# Oscillator.net
KiCad netlist of a schematic drawn in Altium Designer
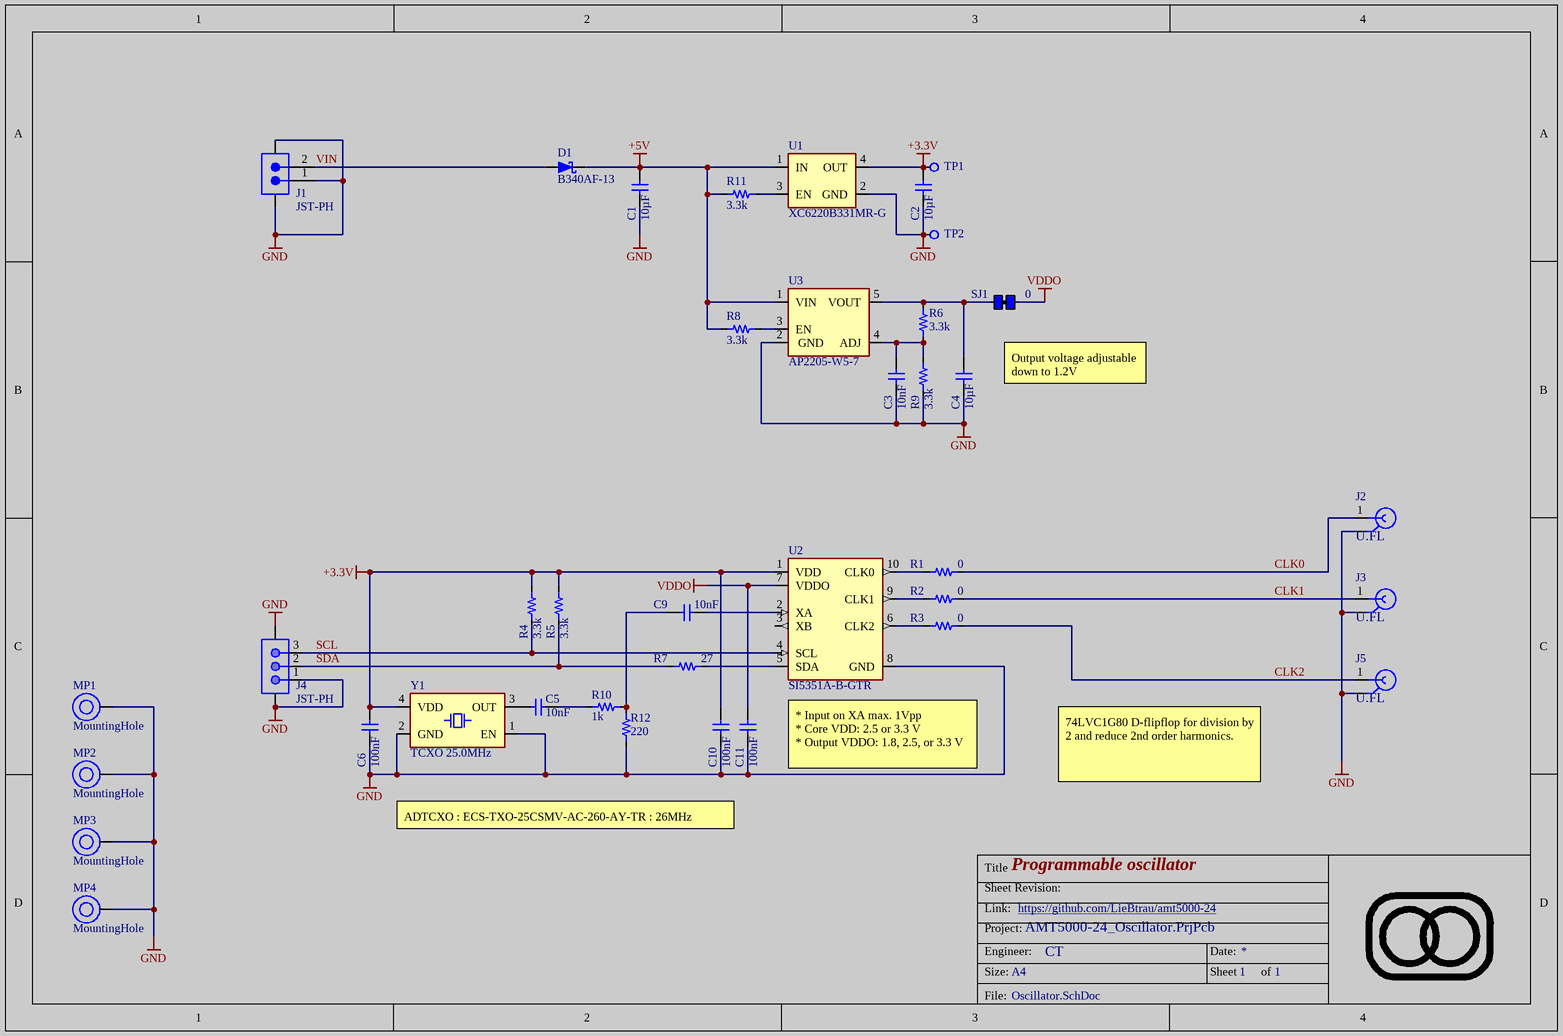
[diagram p0: Oscillator.SchDoc]

(export (version "E")
  (design (tool "Eeschema 10.0.6"))
  (components
    (comp (ref "C1")
      (value "10µF")
      (footprint "1206-C-N")
      (description "WCAP-CSGP Multilayer Ceramic Chip Capacitor, General Purpose, size 1206, X7R, 10µF, 10VDC")
      (fields (field (name "JLCPCB PART #") "C70462") (field (name "TOLERANCE") "10%"))
      (libsource (lib "7c7 Engineering") (part "CAP-NP-2"))
    )
    (comp (ref "C2")
      (value "10µF")
      (footprint "1206-C-N")
      (description "WCAP-CSGP Multilayer Ceramic Chip Capacitor, General Purpose, size 1206, X7R, 10µF, 10VDC")
      (fields (field (name "JLCPCB PART #") "C70462") (field (name "TOLERANCE") "10%"))
      (libsource (lib "7c7 Engineering") (part "CAP-NP-2"))
    )
    (comp (ref "C3")
      (value "10nF")
      (footprint "0603-C-N")
      (description "Multilayer Ceramic Capacitor, Grm Series, 0.01 F, 5%, C0g / Np0, 50 V, 0603 [1608 Metric]")
      (fields (field (name "VOLTAGE") "50V") (field (name "TOLERANCE") "5%"))
      (libsource (lib "7c7 Engineering") (part "CAP-NP-2"))
    )
    (comp (ref "C4")
      (value "10µF")
      (footprint "1206-C-N")
      (description "WCAP-CSGP Multilayer Ceramic Chip Capacitor, General Purpose, size 1206, X7R, 10µF, 10VDC")
      (fields (field (name "JLCPCB PART #") "C70462") (field (name "TOLERANCE") "10%"))
      (libsource (lib "7c7 Engineering") (part "CAP-NP-2"))
    )
    (comp (ref "C5")
      (value "10nF")
      (footprint "0603-C-N")
      (description "Multilayer Ceramic Capacitor, Grm Series, 0.01 F, 5%, C0g / Np0, 50 V, 0603 [1608 Metric]")
      (fields (field (name "VOLTAGE") "50V") (field (name "TOLERANCE") "5%"))
      (libsource (lib "7c7 Engineering") (part "CAP-NP-2"))
    )
    (comp (ref "C6")
      (value "100nF")
      (footprint "0603-C-N")
      (description "WCAP-CSGP Multilayer Ceramic Chip Capacitor, General Purpose, size 0603, X7R, 100nF, 50VDC")
      (fields (field (name "TOLERANCE") "10%") (field (name "JLCPCB PART #") "C14663"))
      (libsource (lib "7c7 Engineering") (part "CAP-NP-2"))
    )
    (comp (ref "C9")
      (value "10nF")
      (footprint "0603-C-N")
      (description "Multilayer Ceramic Capacitor, Grm Series, 0.01 F, 5%, C0g / Np0, 50 V, 0603 [1608 Metric]")
      (fields (field (name "VOLTAGE") "50V") (field (name "TOLERANCE") "5%"))
      (libsource (lib "7c7 Engineering") (part "CAP-NP-2"))
    )
    (comp (ref "C10")
      (value "100nF")
      (footprint "0603-C-N")
      (description "WCAP-CSGP Multilayer Ceramic Chip Capacitor, General Purpose, size 0603, X7R, 100nF, 50VDC")
      (fields (field (name "TOLERANCE") "10%") (field (name "JLCPCB PART #") "C14663"))
      (libsource (lib "7c7 Engineering") (part "CAP-NP-2"))
    )
    (comp (ref "C11")
      (value "100nF")
      (footprint "0603-C-N")
      (description "WCAP-CSGP Multilayer Ceramic Chip Capacitor, General Purpose, size 0603, X7R, 100nF, 50VDC")
      (fields (field (name "TOLERANCE") "10%") (field (name "JLCPCB PART #") "C14663"))
      (libsource (lib "7c7 Engineering") (part "CAP-NP-2"))
    )
    (comp (ref "D1")
      (value "B340AF-13")
      (footprint "DO-214AC_UNI")
      (description "Diode 40 V 3A Surface Mount SMAF")
      (fields (field (name "JLCPCB PART #") "C172880"))
      (libsource (lib "7c7 Engineering") (part "DIODE-SKY-2"))
    )
    (comp (ref "J1")
      (value "JST-PH")
      (footprint "620302124022")
      (description "WR-WTB SMT Male Vertical Shrouded Header, pitch 2mm, 2p")
      (fields
        (field (name "JLCPCB PART #") "C18077899")
        (field (name "PART NUMBER") "620302124022")
        (field (name "PUBLISHER") "Wurth Elektronik")
      )
      (libsource (lib "7c7 Engineering") (part "HDR_2P_2MP"))
    )
    (comp (ref "J2")
      (value "U.FL-R-SMT(10)")
      (footprint "HRS-U.FL-R-SMT_V")
      (fields (field (name "JLCPCB PART #") "C88373") (field (name "MANUFACTURER") "Hirose Electric"))
      (libsource (lib "7c7 Engineering") (part "CN_COAX"))
    )
    (comp (ref "J3")
      (value "U.FL-R-SMT(10)")
      (footprint "HRS-U.FL-R-SMT_V")
      (fields (field (name "JLCPCB PART #") "C88373") (field (name "MANUFACTURER") "Hirose Electric"))
      (libsource (lib "7c7 Engineering") (part "CN_COAX"))
    )
    (comp (ref "J4")
      (value "JST-PH")
      (footprint "620303124022")
      (description "WR-WTB SMT Male Vertical Shrouded Header, pitch 2mm, 3p")
      (fields
        (field (name "JLCPCB PART #") "C160353")
        (field (name "PART NUMBER") "620303124022")
        (field (name "PUBLISHER") "Wurth Elektronik")
      )
      (libsource (lib "7c7 Engineering") (part "HDR_3P_2MP"))
    )
    (comp (ref "J5")
      (value "U.FL-R-SMT(10)")
      (footprint "HRS-U.FL-R-SMT_V")
      (fields (field (name "JLCPCB PART #") "C88373") (field (name "MANUFACTURER") "Hirose Electric"))
      (libsource (lib "7c7 Engineering") (part "CN_COAX"))
    )
    (comp (ref "MP1")
      (value "MountingHole")
      (footprint "PTH-M3D6.5_VIA-RING")
      (libsource (lib "7c7 Engineering") (part "MECH_NO_BOM"))
    )
    (comp (ref "MP2")
      (value "MountingHole")
      (footprint "PTH-M3D6.5_VIA-RING")
      (libsource (lib "7c7 Engineering") (part "MECH_NO_BOM"))
    )
    (comp (ref "MP3")
      (value "MountingHole")
      (footprint "PTH-M3D6.5_VIA-RING")
      (libsource (lib "7c7 Engineering") (part "MECH_NO_BOM"))
    )
    (comp (ref "MP4")
      (value "MountingHole")
      (footprint "PTH-M3D6.5_VIA-RING")
      (libsource (lib "7c7 Engineering") (part "MECH_NO_BOM"))
    )
    (comp (ref "R1")
      (value "0")
      (footprint "0603-R-N")
      (description "Chip Jumper, Thick Film, Jumper, 0603, 100mW, 1A, 0 Ohm, <50 mOhm")
      (fields (field (name "FLIR PART #") "YRES0E-1") (field (name "TOLERANCE") "50 mOhm"))
      (libsource (lib "7c7 Engineering") (part "RES"))
    )
    (comp (ref "R2")
      (value "0")
      (footprint "0603-R-N")
      (description "Chip Jumper, Thick Film, Jumper, 0603, 100mW, 1A, 0 Ohm, <50 mOhm")
      (fields (field (name "FLIR PART #") "YRES0E-1") (field (name "TOLERANCE") "50 mOhm"))
      (libsource (lib "7c7 Engineering") (part "RES"))
    )
    (comp (ref "R3")
      (value "0")
      (footprint "0603-R-N")
      (description "Chip Jumper, Thick Film, Jumper, 0603, 100mW, 1A, 0 Ohm, <50 mOhm")
      (fields (field (name "FLIR PART #") "YRES0E-1") (field (name "TOLERANCE") "50 mOhm"))
      (libsource (lib "7c7 Engineering") (part "RES"))
    )
    (comp (ref "R4")
      (value "3.3k")
      (footprint "0603-R-N")
      (description "Chip Resistor, Thick Film, General Purpose, 0603, 100mW, 50V, 3.3 kOhm, +/-1%")
      (fields (field (name "TOLERANCE") "1%") (field (name "JLCPCB PART #") "C22978"))
      (libsource (lib "7c7 Engineering") (part "RES"))
    )
    (comp (ref "R5")
      (value "3.3k")
      (footprint "0603-R-N")
      (description "Chip Resistor, Thick Film, General Purpose, 0603, 100mW, 50V, 3.3 kOhm, +/-1%")
      (fields (field (name "TOLERANCE") "1%") (field (name "JLCPCB PART #") "C22978"))
      (libsource (lib "7c7 Engineering") (part "RES"))
    )
    (comp (ref "R6")
      (value "3.3k")
      (footprint "0603-R-N")
      (description "Chip Resistor, Thick Film, General Purpose, 0603, 100mW, 50V, 3.3 kOhm, +/-1%")
      (fields (field (name "TOLERANCE") "1%") (field (name "JLCPCB PART #") "C22978"))
      (libsource (lib "7c7 Engineering") (part "RES"))
    )
    (comp (ref "R7")
      (value "27")
      (footprint "0603-R-N")
      (description "Res Thick Film 1.6 x 0.8 mm 27 Ohm 1% 0.1W(1/10W) 100ppm/ C Molded SMD Paper T/R")
      (fields (field (name "PAGE PART #") "ROQF2709") (field (name "TOLERANCE") "1%"))
      (libsource (lib "7c7 Engineering") (part "RES"))
    )
    (comp (ref "R8")
      (value "3.3k")
      (footprint "0603-R-N")
      (description "Chip Resistor, Thick Film, General Purpose, 0603, 100mW, 50V, 3.3 kOhm, +/-1%")
      (fields (field (name "TOLERANCE") "1%") (field (name "JLCPCB PART #") "C22978"))
      (libsource (lib "7c7 Engineering") (part "RES"))
    )
    (comp (ref "R9")
      (value "3.3k")
      (footprint "0603-R-N")
      (description "Chip Resistor, Thick Film, General Purpose, 0603, 100mW, 50V, 3.3 kOhm, +/-1%")
      (fields (field (name "TOLERANCE") "1%") (field (name "JLCPCB PART #") "C22978"))
      (libsource (lib "7c7 Engineering") (part "RES"))
    )
    (comp (ref "R10")
      (value "1k")
      (footprint "0603-R-N")
      (description "Chip Resistor, Thick Film, General Purpose, 0603, 100mW, 50V, 1 kOhm, +/-1%")
      (fields (field (name "JLCPCB PART #") "C21190") (field (name "TOLERANCE") "1%"))
      (libsource (lib "7c7 Engineering") (part "RES"))
    )
    (comp (ref "R11")
      (value "3.3k")
      (footprint "0603-R-N")
      (description "Chip Resistor, Thick Film, General Purpose, 0603, 100mW, 50V, 3.3 kOhm, +/-1%")
      (fields (field (name "TOLERANCE") "1%") (field (name "JLCPCB PART #") "C22978"))
      (libsource (lib "7c7 Engineering") (part "RES"))
    )
    (comp (ref "R12")
      (value "220")
      (footprint "0603-R-N")
      (description "Res Thick Film 0603 220 Ohm 1% 0.1W(1/10W) ±100ppm/C Pad SMD T/R Automotive AEC-Q200")
      (fields (field (name "TOLERANCE") "1%") (field (name "JLCPCB PART #") "C22962"))
      (libsource (lib "7c7 Engineering") (part "RES"))
    )
    (comp (ref "SJ1")
      (value "0")
      (footprint "SJ_0603_1A")
      (description "Solder Jumper, Thick Film, Jumper, 0603, 100mW, 1A, 0 Ohm, <50 mOhm")
      (fields (field (name "JLCPCB PART #") "C876125") (field (name "TOLERANCE") "50 mOhm"))
      (libsource (lib "7c7 Engineering") (part "SJ-C"))
    )
    (comp (ref "TP1")
      (value "Testpad with multiple sizes")
      (footprint "TP_1.5mm_0.3mmHole")
      (description "Testpad land")
      (libsource (lib "7c7 Engineering") (part "Testpad"))
    )
    (comp (ref "TP2")
      (value "Testpad with multiple sizes")
      (footprint "TP_1.5mm_0.3mmHole")
      (description "Testpad land")
      (libsource (lib "7c7 Engineering") (part "Testpad"))
    )
    (comp (ref "U1")
      (value "XC6220B331MR-G")
      (footprint "SOT25-N")
      (description "Fixed LDO 3.3V, 1%, 1A, Iq 108uA, -40°C to 85°C")
      (fields (field (name "JLCPCB PART #") "C86534"))
      (libsource (lib "7c7 Engineering") (part "LDO-with-enable"))
    )
    (comp (ref "U2")
      (value "SI5351A-B-GTR")
      (footprint "VSSOP10-N")
      (description "IC CLK GENERATOR 160MHZ 10MSOP")
      (fields (field (name "JLCPCB PART #") "C504891"))
      (libsource (lib "7c7 Engineering") (part "IC_SI5351A"))
    )
    (comp (ref "U3")
      (value "AP2205-W5-7")
      (footprint "SOT25-N")
      (description "Variable LDO 1.24V - 22V, , 250mA, Iq 2.5mA, -40°C to 125°C")
      (fields (field (name "JLCPCB PART #") "C3001658"))
      (libsource (lib "7c7 Engineering") (part "IC_LDO_EN_REF"))
    )
    (comp (ref "Y1")
      (value "TCXO 25.0MHz")
      (footprint "WE-SPXO_IQXO-791")
      (description "TCXO 25MHz, 3.3V")
      (fields (field (name "JLCPCB PART #") "C5180005") (field (name "Comment") "SX2T25.000B010J020S"))
      (libsource (lib "7c7 Engineering") (part "IC_OSCILLATOR"))
    )
  )
  (nets
    (net (code "1") (name "+3.3V") (class "Default")
      (node (ref "C10") (pin "1") (pinfunction "1_1") (pintype "passive"))
      (node (ref "C2") (pin "2") (pinfunction "2_2") (pintype "passive"))
      (node (ref "C6") (pin "1") (pinfunction "1_1") (pintype "passive"))
      (node (ref "R4") (pin "2") (pinfunction "2_2") (pintype "passive"))
      (node (ref "R5") (pin "2") (pinfunction "2_2") (pintype "passive"))
      (node (ref "TP1") (pin "1") (pinfunction "Pad_1") (pintype "passive"))
      (node (ref "U1") (pin "4") (pinfunction "OUT_4") (pintype "power_in"))
      (node (ref "U2") (pin "1") (pinfunction "VDD_1") (pintype "power_in"))
      (node (ref "Y1") (pin "4") (pinfunction "VDD_4") (pintype "passive"))
    )
    (net (code "2") (name "+5V") (class "Default")
      (node (ref "C1") (pin "2") (pinfunction "2_2") (pintype "passive"))
      (node (ref "D1") (pin "1") (pinfunction "K_1") (pintype "passive"))
      (node (ref "R11") (pin "2") (pinfunction "2_2") (pintype "passive"))
      (node (ref "R8") (pin "2") (pinfunction "2_2") (pintype "passive"))
      (node (ref "U1") (pin "1") (pinfunction "IN_1") (pintype "power_in"))
      (node (ref "U3") (pin "1") (pinfunction "VIN_1") (pintype "power_in"))
    )
    (net (code "3") (name "/CLK0") (class "Default")
      (node (ref "J2") (pin "1") (pinfunction "SIG_1") (pintype "passive"))
      (node (ref "R1") (pin "1") (pinfunction "1_1") (pintype "passive"))
    )
    (net (code "4") (name "/CLK1") (class "Default")
      (node (ref "J3") (pin "1") (pinfunction "SIG_1") (pintype "passive"))
      (node (ref "R2") (pin "1") (pinfunction "1_1") (pintype "passive"))
    )
    (net (code "5") (name "/CLK2") (class "Default")
      (node (ref "J5") (pin "1") (pinfunction "SIG_1") (pintype "passive"))
      (node (ref "R3") (pin "1") (pinfunction "1_1") (pintype "passive"))
    )
    (net (code "6") (name "/SCL") (class "Default")
      (node (ref "J4") (pin "3") (pinfunction "3_3") (pintype "passive"))
      (node (ref "R4") (pin "1") (pinfunction "1_1") (pintype "passive"))
      (node (ref "U2") (pin "4") (pinfunction "SCL_4") (pintype "input"))
    )
    (net (code "7") (name "/SDA") (class "Default")
      (node (ref "J4") (pin "2") (pinfunction "2_2") (pintype "passive"))
      (node (ref "R5") (pin "1") (pinfunction "1_1") (pintype "passive"))
      (node (ref "R7") (pin "1") (pinfunction "1_1") (pintype "passive"))
    )
    (net (code "8") (name "/VIN") (class "Default")
      (node (ref "D1") (pin "2") (pinfunction "A_2") (pintype "passive"))
      (node (ref "J1") (pin "2") (pinfunction "2_2") (pintype "passive"))
    )
    (net (code "9") (name "GND") (class "Default")
      (node (ref "C1") (pin "1") (pinfunction "1_1") (pintype "passive"))
      (node (ref "C10") (pin "2") (pinfunction "2_2") (pintype "passive"))
      (node (ref "C11") (pin "2") (pinfunction "2_2") (pintype "passive"))
      (node (ref "C2") (pin "1") (pinfunction "1_1") (pintype "passive"))
      (node (ref "C3") (pin "1") (pinfunction "1_1") (pintype "passive"))
      (node (ref "C4") (pin "1") (pinfunction "1_1") (pintype "passive"))
      (node (ref "C6") (pin "2") (pinfunction "2_2") (pintype "passive"))
      (node (ref "J1") (pin "1") (pinfunction "1_1") (pintype "passive"))
      (node (ref "J1") (pin "MP1") (pinfunction "MP1_MP1") (pintype "passive"))
      (node (ref "J1") (pin "MP2") (pinfunction "MP2_MP2") (pintype "passive"))
      (node (ref "J2") (pin "2") (pinfunction "GND_2") (pintype "passive"))
      (node (ref "J3") (pin "2") (pinfunction "GND_2") (pintype "passive"))
      (node (ref "J4") (pin "1") (pinfunction "1_1") (pintype "passive"))
      (node (ref "J4") (pin "MP1") (pinfunction "MP1_MP1") (pintype "passive"))
      (node (ref "J4") (pin "MP2") (pinfunction "MP2_MP2") (pintype "passive"))
      (node (ref "J5") (pin "2") (pinfunction "GND_2") (pintype "passive"))
      (node (ref "MP1") (pin "1") (pinfunction "H1_1") (pintype "passive"))
      (node (ref "MP2") (pin "1") (pinfunction "H1_1") (pintype "passive"))
      (node (ref "MP3") (pin "1") (pinfunction "H1_1") (pintype "passive"))
      (node (ref "MP4") (pin "1") (pinfunction "H1_1") (pintype "passive"))
      (node (ref "R12") (pin "1") (pinfunction "1_1") (pintype "passive"))
      (node (ref "R9") (pin "2") (pinfunction "2_2") (pintype "passive"))
      (node (ref "TP2") (pin "1") (pinfunction "Pad_1") (pintype "passive"))
      (node (ref "U1") (pin "2") (pinfunction "GND_2") (pintype "power_in"))
      (node (ref "U2") (pin "8") (pinfunction "GND_8") (pintype "power_in"))
      (node (ref "U3") (pin "2") (pinfunction "GND_2") (pintype "power_in"))
      (node (ref "Y1") (pin "1") (pinfunction "EN_1") (pintype "passive"))
      (node (ref "Y1") (pin "2") (pinfunction "GND_2") (pintype "passive"))
    )
    (net (code "10") (name "Net-(C5-Pad2)") (class "Default")
      (node (ref "C5") (pin "2") (pinfunction "2_2") (pintype "passive"))
      (node (ref "R10") (pin "1") (pinfunction "1_1") (pintype "passive"))
    )
    (net (code "11") (name "Net-(C9-Pad2)") (class "Default")
      (node (ref "C9") (pin "2") (pinfunction "2_2") (pintype "passive"))
      (node (ref "R10") (pin "2") (pinfunction "2_2") (pintype "passive"))
      (node (ref "R12") (pin "2") (pinfunction "2_2") (pintype "passive"))
    )
    (net (code "12") (name "Net-(SJ1-L)") (class "Default")
      (node (ref "C4") (pin "2") (pinfunction "2_2") (pintype "passive"))
      (node (ref "R6") (pin "1") (pinfunction "1_1") (pintype "passive"))
      (node (ref "SJ1") (pin "1") (pinfunction "L_1") (pintype "passive"))
      (node (ref "U3") (pin "5") (pinfunction "VOUT_5") (pintype "power_in"))
    )
    (net (code "13") (name "Net-(U1-EN)") (class "Default")
      (node (ref "R11") (pin "1") (pinfunction "1_1") (pintype "passive"))
      (node (ref "U1") (pin "3") (pinfunction "EN_3") (pintype "passive"))
    )
    (net (code "14") (name "Net-(U2-CLK0)") (class "Default")
      (node (ref "R1") (pin "2") (pinfunction "2_2") (pintype "passive"))
      (node (ref "U2") (pin "10") (pinfunction "CLK0_10") (pintype "output"))
    )
    (net (code "15") (name "Net-(U2-CLK1)") (class "Default")
      (node (ref "R2") (pin "2") (pinfunction "2_2") (pintype "passive"))
      (node (ref "U2") (pin "9") (pinfunction "CLK1_9") (pintype "output"))
    )
    (net (code "16") (name "Net-(U2-CLK2)") (class "Default")
      (node (ref "R3") (pin "2") (pinfunction "2_2") (pintype "passive"))
      (node (ref "U2") (pin "6") (pinfunction "CLK2_6") (pintype "output"))
    )
    (net (code "17") (name "Net-(U2-SDA)") (class "Default")
      (node (ref "R7") (pin "2") (pinfunction "2_2") (pintype "passive"))
      (node (ref "U2") (pin "5") (pinfunction "SDA_5") (pintype "bidirectional"))
    )
    (net (code "18") (name "Net-(U2-XA)") (class "Default")
      (node (ref "C9") (pin "1") (pinfunction "1_1") (pintype "passive"))
      (node (ref "U2") (pin "2") (pinfunction "XA_2") (pintype "input"))
    )
    (net (code "19") (name "Net-(U3-ADJ)") (class "Default")
      (node (ref "C3") (pin "2") (pinfunction "2_2") (pintype "passive"))
      (node (ref "R6") (pin "2") (pinfunction "2_2") (pintype "passive"))
      (node (ref "R9") (pin "1") (pinfunction "1_1") (pintype "passive"))
      (node (ref "U3") (pin "4") (pinfunction "ADJ_4") (pintype "passive"))
    )
    (net (code "20") (name "Net-(U3-EN)") (class "Default")
      (node (ref "R8") (pin "1") (pinfunction "1_1") (pintype "passive"))
      (node (ref "U3") (pin "3") (pinfunction "EN_3") (pintype "passive"))
    )
    (net (code "21") (name "Net-(Y1-OUT)") (class "Default")
      (node (ref "C5") (pin "1") (pinfunction "1_1") (pintype "passive"))
      (node (ref "Y1") (pin "3") (pinfunction "OUT_3") (pintype "passive"))
    )
    (net (code "22") (name "VDDO") (class "Default")
      (node (ref "C11") (pin "1") (pinfunction "1_1") (pintype "passive"))
      (node (ref "SJ1") (pin "2") (pinfunction "R_2") (pintype "passive"))
      (node (ref "U2") (pin "7") (pinfunction "VDDO_7") (pintype "power_in"))
    )
    (net (code "23") (name "unconnected-(U2-XB-Pad3)") (class "Default")
      (node (ref "U2") (pin "3") (pinfunction "XB_3") (pintype "output"))
    )
  )
)
